# RN2483_01.net
KiCad netlist of a schematic drawn in EAGLE
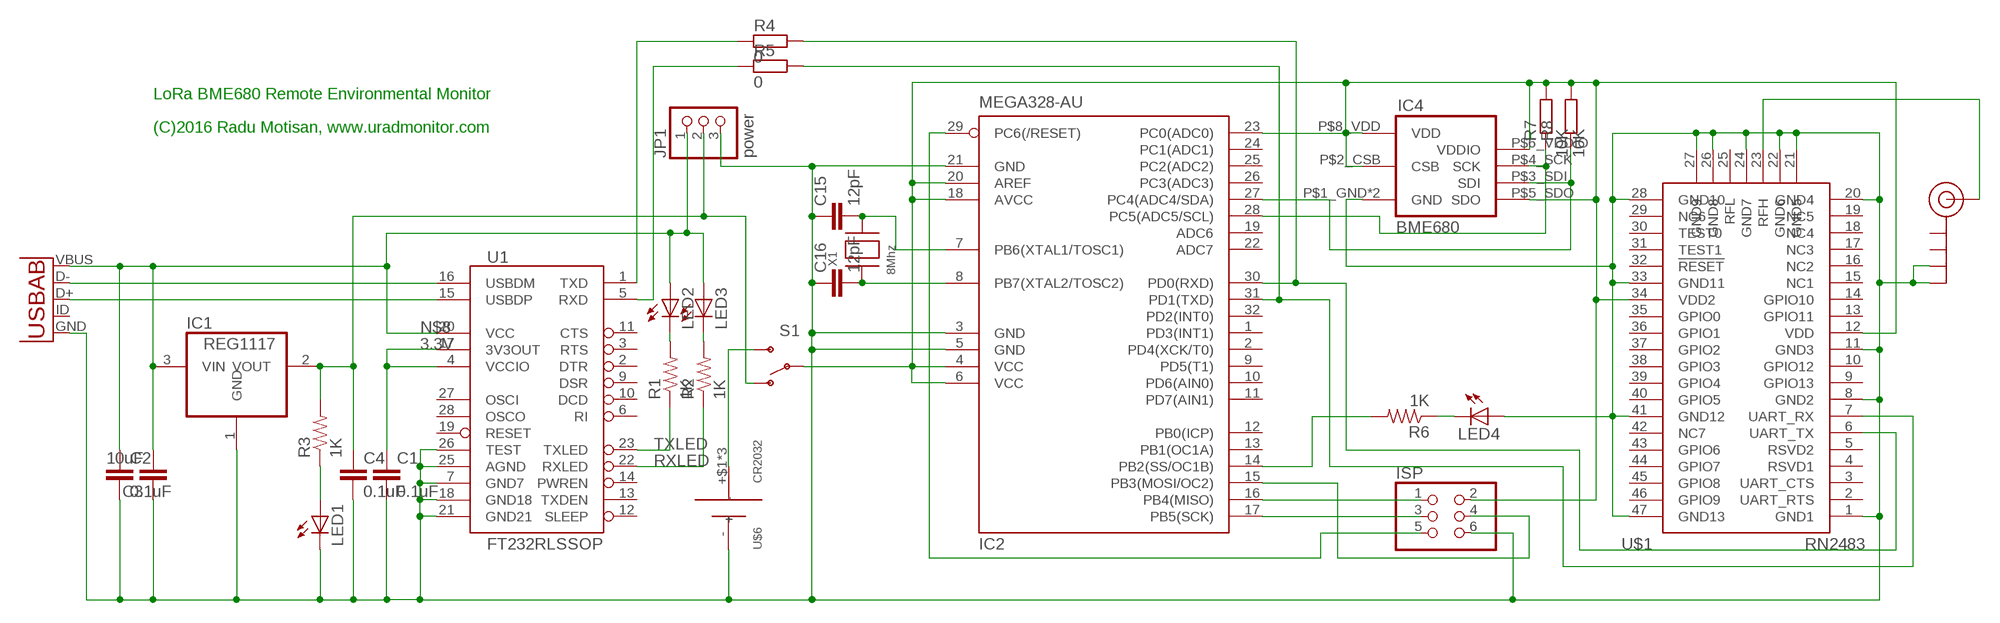
[diagram p0: schematic, sheet 1]

(export (version "E")
  (design (tool "Eeschema 10.0.6"))
  (components
    (comp (ref "C1")
      (value "0.1uF")
      (footprint "eagle-import:0805")
      (libsource (lib "eagle-import") (part "CAP0805"))
    )
    (comp (ref "C2")
      (value "0.1uF")
      (footprint "eagle-import:0805")
      (libsource (lib "eagle-import") (part "CAP0805"))
    )
    (comp (ref "C3")
      (value "10uF")
      (footprint "eagle-import:C0805K")
      (libsource (lib "eagle-import") (part "C-EUC0805K"))
    )
    (comp (ref "C4")
      (value "0.1uF")
      (footprint "eagle-import:0805")
      (libsource (lib "eagle-import") (part "CAP0805"))
    )
    (comp (ref "C15")
      (value "12pF")
      (footprint "eagle-import:C0805K")
      (libsource (lib "eagle-import") (part "C-EUC0805K"))
    )
    (comp (ref "C16")
      (value "12pF")
      (footprint "eagle-import:C0805K")
      (libsource (lib "eagle-import") (part "C-EUC0805K"))
    )
    (comp (ref "IC1")
      (value "REG1117")
      (footprint "eagle-import:SOT223")
      (libsource (lib "eagle-import") (part "REG1117"))
    )
    (comp (ref "IC2")
      (value "MEGA328-AU")
      (footprint "eagle-import:TQFP32-08")
      (fields (field (name "MPN") "ATMEGA8-16AU"))
      (libsource (lib "eagle-import") (part "MEGA8-AI"))
    )
    (comp (ref "IC4")
      (value "BME680")
      (footprint "eagle-import:BME680")
      (libsource (lib "eagle-import") (part "BME680"))
    )
    (comp (ref "ISP")
      (value "PINHD-2X3")
      (footprint "eagle-import:2X03")
      (libsource (lib "eagle-import") (part "PINHD-2X3"))
    )
    (comp (ref "J$1")
      (value "SMA_EDGE")
      (footprint "eagle-import:SMA-EDGE")
      (libsource (lib "eagle-import") (part "SMA_EDGE"))
    )
    (comp (ref "JP1")
      (value "power")
      (footprint "eagle-import:1X03")
      (libsource (lib "eagle-import") (part "PINHD-1X3"))
    )
    (comp (ref "LED1")
      (value "LEDCHIP-LED0805")
      (footprint "eagle-import:CHIP-LED0805")
      (libsource (lib "eagle-import") (part "LEDCHIP-LED0805"))
    )
    (comp (ref "LED2")
      (value "LEDCHIP-LED0805")
      (footprint "eagle-import:CHIP-LED0805")
      (libsource (lib "eagle-import") (part "LEDCHIP-LED0805"))
    )
    (comp (ref "LED3")
      (value "LEDCHIP-LED0805")
      (footprint "eagle-import:CHIP-LED0805")
      (libsource (lib "eagle-import") (part "LEDCHIP-LED0805"))
    )
    (comp (ref "LED4")
      (value "LEDCHIP-LED0805")
      (footprint "eagle-import:CHIP-LED0805")
      (libsource (lib "eagle-import") (part "LEDCHIP-LED0805"))
    )
    (comp (ref "R1")
      (value "1K")
      (footprint "eagle-import:0805")
      (libsource (lib "eagle-import") (part "RESISTOR0805-RES"))
    )
    (comp (ref "R2")
      (value "1K")
      (footprint "eagle-import:0805")
      (libsource (lib "eagle-import") (part "RESISTOR0805-RES"))
    )
    (comp (ref "R3")
      (value "1K")
      (footprint "eagle-import:0805")
      (libsource (lib "eagle-import") (part "RESISTOR0805-RES"))
    )
    (comp (ref "R4")
      (value "0")
      (footprint "eagle-import:R0805")
      (libsource (lib "eagle-import") (part "R-EU_R0805"))
    )
    (comp (ref "R5")
      (value "0")
      (footprint "eagle-import:R0805")
      (libsource (lib "eagle-import") (part "R-EU_R0805"))
    )
    (comp (ref "R6")
      (value "1K")
      (footprint "eagle-import:0805")
      (libsource (lib "eagle-import") (part "RESISTOR0805-RES"))
    )
    (comp (ref "R7")
      (value "10K")
      (footprint "eagle-import:R0805")
      (libsource (lib "eagle-import") (part "R-EU_R0805"))
    )
    (comp (ref "R8")
      (value "10K")
      (footprint "eagle-import:R0805")
      (libsource (lib "eagle-import") (part "R-EU_R0805"))
    )
    (comp (ref "S1")
      (value "SWITCH-SPDT-SMD-A")
      (footprint "eagle-import:SWITCH-SPST-SMD-A")
      (libsource (lib "eagle-import") (part "SWITCH-SPDT-SMD-A"))
    )
    (comp (ref "U$1")
      (value "RN2483")
      (footprint "eagle-import:RN2483")
      (libsource (lib "eagle-import") (part "RN2483"))
    )
    (comp (ref "U$2")
      (value "USB_AB")
      (footprint "eagle-import:USB-AB-MICRO-SMD")
      (libsource (lib "eagle-import") (part "USB_AB"))
    )
    (comp (ref "U$6")
      (value "CR2032")
      (footprint "eagle-import:CR2032")
      (libsource (lib "eagle-import") (part "CR2032"))
    )
    (comp (ref "U1")
      (value "FT232RLSSOP")
      (footprint "eagle-import:SSOP28DB")
      (libsource (lib "eagle-import") (part "FT232RLSSOP"))
    )
    (comp (ref "X1")
      (value "8Mhz")
      (footprint "eagle-import:NX5032")
      (libsource (lib "eagle-import") (part "XTALNX5032"))
    )
  )
  (nets
    (net (code "1") (name "/3.3V") (class "Default")
      (node (ref "C1") (pin "1") (pinfunction "1_1") (pintype "passive"))
      (node (ref "U1") (pin "17") (pinfunction "3V3OUT_17") (pintype "output"))
      (node (ref "U1") (pin "4") (pinfunction "VCCIO_4") (pintype "power_in"))
    )
    (net (code "2") (name "/N$8") (class "Default")
      (node (ref "C2") (pin "1") (pinfunction "1_1") (pintype "passive"))
      (node (ref "C3") (pin "2") (pinfunction "2_2") (pintype "passive"))
      (node (ref "IC1") (pin "3") (pinfunction "VIN_3") (pintype "input"))
      (node (ref "JP1") (pin "1") (pinfunction "1_1") (pintype "passive"))
      (node (ref "LED2") (pin "A") (pinfunction "A_A") (pintype "passive"))
      (node (ref "LED3") (pin "A") (pinfunction "A_A") (pintype "passive"))
      (node (ref "U$2") (pin "VBUS") (pinfunction "VBUS_VBUS") (pintype "bidirectional"))
      (node (ref "U1") (pin "20") (pinfunction "VCC_20") (pintype "power_in"))
    )
    (net (code "3") (name "/RXLED") (class "Default")
      (node (ref "R2") (pin "1") (pinfunction "1_1") (pintype "passive"))
      (node (ref "U1") (pin "22") (pinfunction "RXLED_22") (pintype "input"))
    )
    (net (code "4") (name "/TXLED") (class "Default")
      (node (ref "R1") (pin "1") (pinfunction "1_1") (pintype "passive"))
      (node (ref "U1") (pin "23") (pinfunction "TXLED_23") (pintype "input"))
    )
    (net (code "5") (name "Net-(IC1-GND)") (class "Default")
      (node (ref "C1") (pin "2") (pinfunction "2_2") (pintype "passive"))
      (node (ref "C15") (pin "1") (pinfunction "1_1") (pintype "passive"))
      (node (ref "C16") (pin "1") (pinfunction "1_1") (pintype "passive"))
      (node (ref "C2") (pin "2") (pinfunction "2_2") (pintype "passive"))
      (node (ref "C3") (pin "1") (pinfunction "1_1") (pintype "passive"))
      (node (ref "C4") (pin "2") (pinfunction "2_2") (pintype "passive"))
      (node (ref "IC1") (pin "1") (pinfunction "GND_1") (pintype "power_in"))
      (node (ref "IC2") (pin "21") (pinfunction "GND_21") (pintype "power_in"))
      (node (ref "IC2") (pin "3") (pinfunction "GND_3") (pintype "power_in"))
      (node (ref "IC2") (pin "5") (pinfunction "GND_5") (pintype "power_in"))
      (node (ref "IC4") (pin "P$1_GND") (pinfunction "GND_P$1_GND") (pintype "power_in"))
      (node (ref "IC4") (pin "P$7_GND") (pinfunction "GND_P$7_GND") (pintype "power_in"))
      (node (ref "ISP") (pin "6") (pinfunction "6_6") (pintype "passive"))
      (node (ref "J$1") (pin "GND@2") (pinfunction "GND_GND@2") (pintype "bidirectional"))
      (node (ref "J$1") (pin "GND@3") (pinfunction "GND_GND@3") (pintype "bidirectional"))
      (node (ref "JP1") (pin "3") (pinfunction "3_3") (pintype "passive"))
      (node (ref "LED1") (pin "C") (pinfunction "C_C") (pintype "passive"))
      (node (ref "LED4") (pin "A") (pinfunction "A_A") (pintype "passive"))
      (node (ref "U$1") (pin "1") (pinfunction "GND1_1") (pintype "bidirectional"))
      (node (ref "U$1") (pin "11") (pinfunction "GND3_11") (pintype "bidirectional"))
      (node (ref "U$1") (pin "20") (pinfunction "GND4_20") (pintype "bidirectional"))
      (node (ref "U$1") (pin "21") (pinfunction "GND5_21") (pintype "bidirectional"))
      (node (ref "U$1") (pin "22") (pinfunction "GND6_22") (pintype "bidirectional"))
      (node (ref "U$1") (pin "24") (pinfunction "GND7_24") (pintype "bidirectional"))
      (node (ref "U$1") (pin "26") (pinfunction "GND8_26") (pintype "bidirectional"))
      (node (ref "U$1") (pin "27") (pinfunction "GND9_27") (pintype "bidirectional"))
      (node (ref "U$1") (pin "28") (pinfunction "GND10_28") (pintype "bidirectional"))
      (node (ref "U$1") (pin "33") (pinfunction "GND11_33") (pintype "bidirectional"))
      (node (ref "U$1") (pin "41") (pinfunction "GND12_41") (pintype "bidirectional"))
      (node (ref "U$1") (pin "47") (pinfunction "GND13_47") (pintype "bidirectional"))
      (node (ref "U$1") (pin "8") (pinfunction "GND2_8") (pintype "bidirectional"))
      (node (ref "U$2") (pin "GND") (pinfunction "GND_GND") (pintype "bidirectional"))
      (node (ref "U$6") (pin "-") (pinfunction "-_-") (pintype "power_in"))
      (node (ref "U1") (pin "18") (pinfunction "GND18_18") (pintype "power_in"))
      (node (ref "U1") (pin "21") (pinfunction "GND21_21") (pintype "power_in"))
      (node (ref "U1") (pin "25") (pinfunction "AGND_25") (pintype "power_in"))
      (node (ref "U1") (pin "26") (pinfunction "TEST_26") (pintype "input"))
      (node (ref "U1") (pin "7") (pinfunction "GND7_7") (pintype "power_in"))
    )
    (net (code "6") (name "Net-(IC1-VOUT)") (class "Default")
      (node (ref "C4") (pin "1") (pinfunction "1_1") (pintype "passive"))
      (node (ref "IC1") (pin "2") (pinfunction "VOUT_2") (pintype "output"))
      (node (ref "JP1") (pin "2") (pinfunction "2_2") (pintype "passive"))
      (node (ref "R3") (pin "2") (pinfunction "2_2") (pintype "passive"))
      (node (ref "S1") (pin "1") (pinfunction "O_1") (pintype "passive"))
    )
    (net (code "7") (name "Net-(IC2-AREF)") (class "Default")
      (node (ref "IC2") (pin "18") (pinfunction "AVCC_18") (pintype "power_in"))
      (node (ref "IC2") (pin "20") (pinfunction "AREF_20") (pintype "passive"))
      (node (ref "IC2") (pin "23") (pinfunction "PC0(ADC0)_23") (pintype "bidirectional"))
      (node (ref "IC2") (pin "4") (pinfunction "VCC_4") (pintype "power_in"))
      (node (ref "IC2") (pin "6") (pinfunction "VCC_6") (pintype "power_in"))
      (node (ref "IC4") (pin "P$2_CSB") (pinfunction "CSB_P$2_CSB") (pintype "input"))
      (node (ref "IC4") (pin "P$5_SDO") (pinfunction "SDO_P$5_SDO") (pintype "input"))
      (node (ref "IC4") (pin "P$6_VDDIO") (pinfunction "VDDIO_P$6_VDDIO") (pintype "power_in"))
      (node (ref "IC4") (pin "P$8_VDD") (pinfunction "VDD_P$8_VDD") (pintype "power_in"))
      (node (ref "ISP") (pin "2") (pinfunction "2_2") (pintype "passive"))
      (node (ref "R7") (pin "2") (pinfunction "2_2") (pintype "passive"))
      (node (ref "R8") (pin "2") (pinfunction "2_2") (pintype "passive"))
      (node (ref "S1") (pin "2") (pinfunction "P_2") (pintype "passive"))
      (node (ref "U$1") (pin "12") (pinfunction "VDD_12") (pintype "bidirectional"))
      (node (ref "U$1") (pin "34") (pinfunction "VDD2_34") (pintype "bidirectional"))
    )
    (net (code "8") (name "Net-(IC2-PB2(SS{slash}OC1B))") (class "Default")
      (node (ref "IC2") (pin "14") (pinfunction "PB2(SS/OC1B)_14") (pintype "bidirectional"))
      (node (ref "R6") (pin "2") (pinfunction "2_2") (pintype "passive"))
    )
    (net (code "9") (name "Net-(IC2-PB3(MOSI{slash}OC2))") (class "Default")
      (node (ref "IC2") (pin "15") (pinfunction "PB3(MOSI/OC2)_15") (pintype "bidirectional"))
      (node (ref "ISP") (pin "4") (pinfunction "4_4") (pintype "passive"))
    )
    (net (code "10") (name "Net-(IC2-PB4(MISO))") (class "Default")
      (node (ref "IC2") (pin "16") (pinfunction "PB4(MISO)_16") (pintype "bidirectional"))
      (node (ref "ISP") (pin "1") (pinfunction "1_1") (pintype "passive"))
    )
    (net (code "11") (name "Net-(IC2-PB5(SCK))") (class "Default")
      (node (ref "IC2") (pin "17") (pinfunction "PB5(SCK)_17") (pintype "bidirectional"))
      (node (ref "ISP") (pin "3") (pinfunction "3_3") (pintype "passive"))
    )
    (net (code "12") (name "Net-(IC2-PB6(XTAL1{slash}TOSC1))") (class "Default")
      (node (ref "C15") (pin "2") (pinfunction "2_2") (pintype "passive"))
      (node (ref "IC2") (pin "7") (pinfunction "PB6(XTAL1/TOSC1)_7") (pintype "bidirectional"))
      (node (ref "X1") (pin "P$2") (pinfunction "P$2_P$2") (pintype "bidirectional"))
    )
    (net (code "13") (name "Net-(IC2-PB7(XTAL2{slash}TOSC2))") (class "Default")
      (node (ref "C16") (pin "2") (pinfunction "2_2") (pintype "passive"))
      (node (ref "IC2") (pin "8") (pinfunction "PB7(XTAL2/TOSC2)_8") (pintype "bidirectional"))
      (node (ref "X1") (pin "P$1") (pinfunction "P$1_P$1") (pintype "bidirectional"))
    )
    (net (code "14") (name "Net-(IC2-PC4(ADC4{slash}SDA))") (class "Default")
      (node (ref "IC2") (pin "27") (pinfunction "PC4(ADC4/SDA)_27") (pintype "bidirectional"))
      (node (ref "IC4") (pin "P$3_SDI") (pinfunction "SDI_P$3_SDI") (pintype "bidirectional"))
      (node (ref "R8") (pin "1") (pinfunction "1_1") (pintype "passive"))
    )
    (net (code "15") (name "Net-(IC2-PC5(ADC5{slash}SCL))") (class "Default")
      (node (ref "IC2") (pin "28") (pinfunction "PC5(ADC5/SCL)_28") (pintype "bidirectional"))
      (node (ref "IC4") (pin "P$4_SCK") (pinfunction "SCK_P$4_SCK") (pintype "bidirectional"))
      (node (ref "R7") (pin "1") (pinfunction "1_1") (pintype "passive"))
    )
    (net (code "16") (name "Net-(IC2-PC6({slash}RESET))") (class "Default")
      (node (ref "IC2") (pin "29") (pinfunction "PC6(/RESET)_29") (pintype "bidirectional"))
      (node (ref "ISP") (pin "5") (pinfunction "5_5") (pintype "passive"))
    )
    (net (code "17") (name "Net-(IC2-PD0(RXD))") (class "Default")
      (node (ref "IC2") (pin "30") (pinfunction "PD0(RXD)_30") (pintype "bidirectional"))
      (node (ref "R4") (pin "2") (pinfunction "2_2") (pintype "passive"))
      (node (ref "U$1") (pin "6") (pinfunction "UART_TX_6") (pintype "bidirectional"))
    )
    (net (code "18") (name "Net-(IC2-PD1(TXD))") (class "Default")
      (node (ref "IC2") (pin "31") (pinfunction "PD1(TXD)_31") (pintype "bidirectional"))
      (node (ref "R5") (pin "2") (pinfunction "2_2") (pintype "passive"))
      (node (ref "U$1") (pin "7") (pinfunction "UART_RX_7") (pintype "bidirectional"))
    )
    (net (code "19") (name "Net-(J$1-SIGNAL)") (class "Default")
      (node (ref "J$1") (pin "SIG") (pinfunction "SIGNAL_SIG") (pintype "bidirectional"))
      (node (ref "U$1") (pin "23") (pinfunction "RFH_23") (pintype "bidirectional"))
    )
    (net (code "20") (name "Net-(LED1-PadA)") (class "Default")
      (node (ref "LED1") (pin "A") (pinfunction "A_A") (pintype "passive"))
      (node (ref "R3") (pin "1") (pinfunction "1_1") (pintype "passive"))
    )
    (net (code "21") (name "Net-(LED2-PadC)") (class "Default")
      (node (ref "LED2") (pin "C") (pinfunction "C_C") (pintype "passive"))
      (node (ref "R1") (pin "2") (pinfunction "2_2") (pintype "passive"))
    )
    (net (code "22") (name "Net-(LED3-PadC)") (class "Default")
      (node (ref "LED3") (pin "C") (pinfunction "C_C") (pintype "passive"))
      (node (ref "R2") (pin "2") (pinfunction "2_2") (pintype "passive"))
    )
    (net (code "23") (name "Net-(LED4-PadC)") (class "Default")
      (node (ref "LED4") (pin "C") (pinfunction "C_C") (pintype "passive"))
      (node (ref "R6") (pin "1") (pinfunction "1_1") (pintype "passive"))
    )
    (net (code "24") (name "Net-(S1-S)") (class "Default")
      (node (ref "S1") (pin "3") (pinfunction "S_3") (pintype "passive"))
      (node (ref "U$6") (pin "+$1") (pinfunction "+_+$1") (pintype "power_in"))
      (node (ref "U$6") (pin "+$2") (pinfunction "+_+$2") (pintype "power_in"))
      (node (ref "U$6") (pin "+$3") (pinfunction "+_+$3") (pintype "power_in"))
    )
    (net (code "25") (name "Net-(U1-RXD)") (class "Default")
      (node (ref "R5") (pin "1") (pinfunction "1_1") (pintype "passive"))
      (node (ref "U1") (pin "5") (pinfunction "RXD_5") (pintype "input"))
    )
    (net (code "26") (name "Net-(U1-TXD)") (class "Default")
      (node (ref "R4") (pin "1") (pinfunction "1_1") (pintype "passive"))
      (node (ref "U1") (pin "1") (pinfunction "TXD_1") (pintype "output"))
    )
    (net (code "27") (name "Net-(U1-USBDM)") (class "Default")
      (node (ref "U$2") (pin "D-") (pinfunction "D-_D-") (pintype "bidirectional"))
      (node (ref "U1") (pin "16") (pinfunction "USBDM_16") (pintype "bidirectional"))
    )
    (net (code "28") (name "Net-(U1-USBDP)") (class "Default")
      (node (ref "U$2") (pin "D+") (pinfunction "D+_D+") (pintype "bidirectional"))
      (node (ref "U1") (pin "15") (pinfunction "USBDP_15") (pintype "bidirectional"))
    )
    (net (code "29") (name "unconnected-(IC2-ADC6-Pad19)") (class "Default")
      (node (ref "IC2") (pin "19") (pinfunction "ADC6_19") (pintype "bidirectional"))
    )
    (net (code "30") (name "unconnected-(IC2-ADC7-Pad22)") (class "Default")
      (node (ref "IC2") (pin "22") (pinfunction "ADC7_22") (pintype "bidirectional"))
    )
    (net (code "31") (name "unconnected-(IC2-PB0(ICP)-Pad12)") (class "Default")
      (node (ref "IC2") (pin "12") (pinfunction "PB0(ICP)_12") (pintype "bidirectional"))
    )
    (net (code "32") (name "unconnected-(IC2-PB1(OC1A)-Pad13)") (class "Default")
      (node (ref "IC2") (pin "13") (pinfunction "PB1(OC1A)_13") (pintype "bidirectional"))
    )
    (net (code "33") (name "unconnected-(IC2-PC1(ADC1)-Pad24)") (class "Default")
      (node (ref "IC2") (pin "24") (pinfunction "PC1(ADC1)_24") (pintype "bidirectional"))
    )
    (net (code "34") (name "unconnected-(IC2-PC2(ADC2)-Pad25)") (class "Default")
      (node (ref "IC2") (pin "25") (pinfunction "PC2(ADC2)_25") (pintype "bidirectional"))
    )
    (net (code "35") (name "unconnected-(IC2-PC3(ADC3)-Pad26)") (class "Default")
      (node (ref "IC2") (pin "26") (pinfunction "PC3(ADC3)_26") (pintype "bidirectional"))
    )
    (net (code "36") (name "unconnected-(IC2-PD2(INT0)-Pad32)") (class "Default")
      (node (ref "IC2") (pin "32") (pinfunction "PD2(INT0)_32") (pintype "bidirectional"))
    )
    (net (code "37") (name "unconnected-(IC2-PD3(INT1)-Pad1)") (class "Default")
      (node (ref "IC2") (pin "1") (pinfunction "PD3(INT1)_1") (pintype "bidirectional"))
    )
    (net (code "38") (name "unconnected-(IC2-PD4(XCK{slash}T0)-Pad2)") (class "Default")
      (node (ref "IC2") (pin "2") (pinfunction "PD4(XCK/T0)_2") (pintype "bidirectional"))
    )
    (net (code "39") (name "unconnected-(IC2-PD5(T1)-Pad9)") (class "Default")
      (node (ref "IC2") (pin "9") (pinfunction "PD5(T1)_9") (pintype "bidirectional"))
    )
    (net (code "40") (name "unconnected-(IC2-PD6(AIN0)-Pad10)") (class "Default")
      (node (ref "IC2") (pin "10") (pinfunction "PD6(AIN0)_10") (pintype "bidirectional"))
    )
    (net (code "41") (name "unconnected-(IC2-PD7(AIN1)-Pad11)") (class "Default")
      (node (ref "IC2") (pin "11") (pinfunction "PD7(AIN1)_11") (pintype "bidirectional"))
    )
    (net (code "42") (name "unconnected-(J$1-GND-PadGND@0)") (class "Default")
      (node (ref "J$1") (pin "GND@0") (pinfunction "GND_GND@0") (pintype "bidirectional"))
    )
    (net (code "43") (name "unconnected-(J$1-GND-PadGND@1)") (class "Default")
      (node (ref "J$1") (pin "GND@1") (pinfunction "GND_GND@1") (pintype "bidirectional"))
    )
    (net (code "44") (name "unconnected-(U$1-GPIO0-Pad35)") (class "Default")
      (node (ref "U$1") (pin "35") (pinfunction "GPIO0_35") (pintype "bidirectional"))
    )
    (net (code "45") (name "unconnected-(U$1-GPIO1-Pad36)") (class "Default")
      (node (ref "U$1") (pin "36") (pinfunction "GPIO1_36") (pintype "bidirectional"))
    )
    (net (code "46") (name "unconnected-(U$1-GPIO2-Pad37)") (class "Default")
      (node (ref "U$1") (pin "37") (pinfunction "GPIO2_37") (pintype "bidirectional"))
    )
    (net (code "47") (name "unconnected-(U$1-GPIO3-Pad38)") (class "Default")
      (node (ref "U$1") (pin "38") (pinfunction "GPIO3_38") (pintype "bidirectional"))
    )
    (net (code "48") (name "unconnected-(U$1-GPIO4-Pad39)") (class "Default")
      (node (ref "U$1") (pin "39") (pinfunction "GPIO4_39") (pintype "bidirectional"))
    )
    (net (code "49") (name "unconnected-(U$1-GPIO5-Pad40)") (class "Default")
      (node (ref "U$1") (pin "40") (pinfunction "GPIO5_40") (pintype "bidirectional"))
    )
    (net (code "50") (name "unconnected-(U$1-GPIO6-Pad43)") (class "Default")
      (node (ref "U$1") (pin "43") (pinfunction "GPIO6_43") (pintype "bidirectional"))
    )
    (net (code "51") (name "unconnected-(U$1-GPIO7-Pad44)") (class "Default")
      (node (ref "U$1") (pin "44") (pinfunction "GPIO7_44") (pintype "bidirectional"))
    )
    (net (code "52") (name "unconnected-(U$1-GPIO8-Pad45)") (class "Default")
      (node (ref "U$1") (pin "45") (pinfunction "GPIO8_45") (pintype "bidirectional"))
    )
    (net (code "53") (name "unconnected-(U$1-GPIO9-Pad46)") (class "Default")
      (node (ref "U$1") (pin "46") (pinfunction "GPIO9_46") (pintype "bidirectional"))
    )
    (net (code "54") (name "unconnected-(U$1-GPIO10-Pad14)") (class "Default")
      (node (ref "U$1") (pin "14") (pinfunction "GPIO10_14") (pintype "bidirectional"))
    )
    (net (code "55") (name "unconnected-(U$1-GPIO11-Pad13)") (class "Default")
      (node (ref "U$1") (pin "13") (pinfunction "GPIO11_13") (pintype "bidirectional"))
    )
    (net (code "56") (name "unconnected-(U$1-GPIO12-Pad10)") (class "Default")
      (node (ref "U$1") (pin "10") (pinfunction "GPIO12_10") (pintype "bidirectional"))
    )
    (net (code "57") (name "unconnected-(U$1-GPIO13-Pad9)") (class "Default")
      (node (ref "U$1") (pin "9") (pinfunction "GPIO13_9") (pintype "bidirectional"))
    )
    (net (code "58") (name "unconnected-(U$1-NC1-Pad15)") (class "Default")
      (node (ref "U$1") (pin "15") (pinfunction "NC1_15") (pintype "bidirectional"))
    )
    (net (code "59") (name "unconnected-(U$1-NC2-Pad16)") (class "Default")
      (node (ref "U$1") (pin "16") (pinfunction "NC2_16") (pintype "bidirectional"))
    )
    (net (code "60") (name "unconnected-(U$1-NC3-Pad17)") (class "Default")
      (node (ref "U$1") (pin "17") (pinfunction "NC3_17") (pintype "bidirectional"))
    )
    (net (code "61") (name "unconnected-(U$1-NC4-Pad18)") (class "Default")
      (node (ref "U$1") (pin "18") (pinfunction "NC4_18") (pintype "bidirectional"))
    )
    (net (code "62") (name "unconnected-(U$1-NC5-Pad19)") (class "Default")
      (node (ref "U$1") (pin "19") (pinfunction "NC5_19") (pintype "bidirectional"))
    )
    (net (code "63") (name "unconnected-(U$1-NC6-Pad29)") (class "Default")
      (node (ref "U$1") (pin "29") (pinfunction "NC6_29") (pintype "bidirectional"))
    )
    (net (code "64") (name "unconnected-(U$1-NC7-Pad42)") (class "Default")
      (node (ref "U$1") (pin "42") (pinfunction "NC7_42") (pintype "bidirectional"))
    )
    (net (code "65") (name "unconnected-(U$1-RFL-Pad25)") (class "Default")
      (node (ref "U$1") (pin "25") (pinfunction "RFL_25") (pintype "bidirectional"))
    )
    (net (code "66") (name "unconnected-(U$1-RSVD1-Pad4)") (class "Default")
      (node (ref "U$1") (pin "4") (pinfunction "RSVD1_4") (pintype "bidirectional"))
    )
    (net (code "67") (name "unconnected-(U$1-RSVD2-Pad5)") (class "Default")
      (node (ref "U$1") (pin "5") (pinfunction "RSVD2_5") (pintype "bidirectional"))
    )
    (net (code "68") (name "unconnected-(U$1-TEST0-Pad30)") (class "Default")
      (node (ref "U$1") (pin "30") (pinfunction "TEST0_30") (pintype "bidirectional"))
    )
    (net (code "69") (name "unconnected-(U$1-TEST1-Pad31)") (class "Default")
      (node (ref "U$1") (pin "31") (pinfunction "TEST1_31") (pintype "bidirectional"))
    )
    (net (code "70") (name "unconnected-(U$1-UART_CTS-Pad3)") (class "Default")
      (node (ref "U$1") (pin "3") (pinfunction "UART_CTS_3") (pintype "bidirectional"))
    )
    (net (code "71") (name "unconnected-(U$1-UART_RTS-Pad2)") (class "Default")
      (node (ref "U$1") (pin "2") (pinfunction "UART_RTS_2") (pintype "bidirectional"))
    )
    (net (code "72") (name "unconnected-(U$1-~{RESET}-Pad32)") (class "Default")
      (node (ref "U$1") (pin "32") (pinfunction "~{RESET}_32") (pintype "bidirectional"))
    )
    (net (code "73") (name "unconnected-(U$2-USBID-PadID)") (class "Default")
      (node (ref "U$2") (pin "ID") (pinfunction "USBID_ID") (pintype "bidirectional"))
    )
    (net (code "74") (name "unconnected-(U1-CTS-Pad11)") (class "Default")
      (node (ref "U1") (pin "11") (pinfunction "CTS_11") (pintype "input"))
    )
    (net (code "75") (name "unconnected-(U1-DCD-Pad10)") (class "Default")
      (node (ref "U1") (pin "10") (pinfunction "DCD_10") (pintype "input"))
    )
    (net (code "76") (name "unconnected-(U1-DSR-Pad9)") (class "Default")
      (node (ref "U1") (pin "9") (pinfunction "DSR_9") (pintype "input"))
    )
    (net (code "77") (name "unconnected-(U1-DTR-Pad2)") (class "Default")
      (node (ref "U1") (pin "2") (pinfunction "DTR_2") (pintype "output"))
    )
    (net (code "78") (name "unconnected-(U1-OSCI-Pad27)") (class "Default")
      (node (ref "U1") (pin "27") (pinfunction "OSCI_27") (pintype "input"))
    )
    (net (code "79") (name "unconnected-(U1-OSCO-Pad28)") (class "Default")
      (node (ref "U1") (pin "28") (pinfunction "OSCO_28") (pintype "output"))
    )
    (net (code "80") (name "unconnected-(U1-PWREN-Pad14)") (class "Default")
      (node (ref "U1") (pin "14") (pinfunction "PWREN_14") (pintype "input"))
    )
    (net (code "81") (name "unconnected-(U1-RESET-Pad19)") (class "Default")
      (node (ref "U1") (pin "19") (pinfunction "RESET_19") (pintype "input"))
    )
    (net (code "82") (name "unconnected-(U1-RI-Pad6)") (class "Default")
      (node (ref "U1") (pin "6") (pinfunction "RI_6") (pintype "input"))
    )
    (net (code "83") (name "unconnected-(U1-RTS-Pad3)") (class "Default")
      (node (ref "U1") (pin "3") (pinfunction "RTS_3") (pintype "output"))
    )
    (net (code "84") (name "unconnected-(U1-SLEEP-Pad12)") (class "Default")
      (node (ref "U1") (pin "12") (pinfunction "SLEEP_12") (pintype "input"))
    )
    (net (code "85") (name "unconnected-(U1-TXDEN-Pad13)") (class "Default")
      (node (ref "U1") (pin "13") (pinfunction "TXDEN_13") (pintype "input"))
    )
  )
)
